# M060A.net
KiCad netlist of a schematic drawn in EAGLE
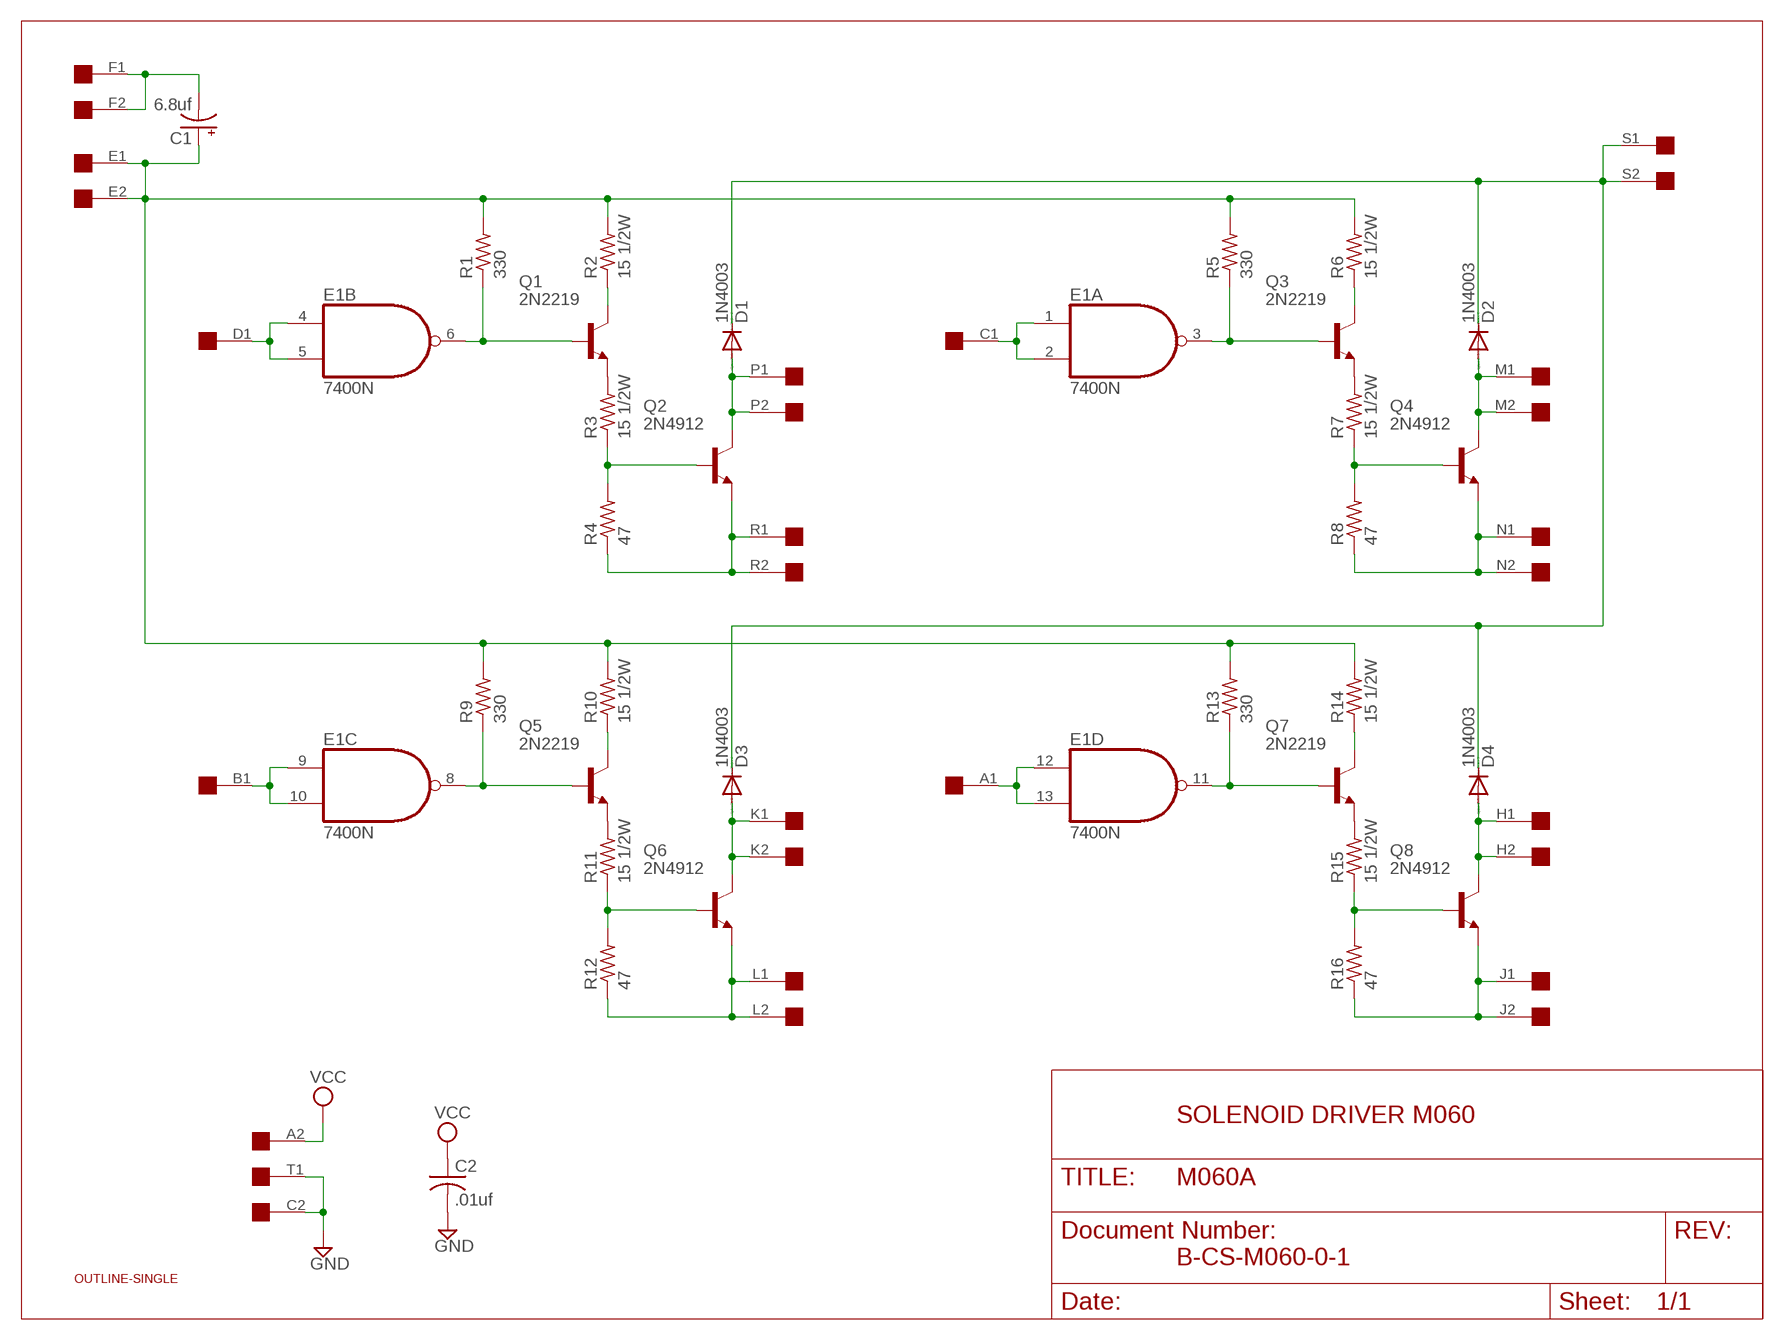
[diagram p0: schematic, sheet 1]

(export (version "E")
  (design (tool "Eeschema 10.0.6"))
  (components
    (comp (ref "C1")
      (value "6.8uf")
      (footprint "eagle-import:E15-5")
      (libsource (lib "eagle-import") (part "CPOL-USE15-5AXIAL"))
    )
    (comp (ref "C2")
      (value ".01uf")
      (footprint "eagle-import:C050-025X075")
      (libsource (lib "eagle-import") (part "C-US050-025X075"))
    )
    (comp (ref "D1")
      (value "1N4003")
      (footprint "eagle-import:DO41-10")
      (libsource (lib "eagle-import") (part "1N4004"))
    )
    (comp (ref "D2")
      (value "1N4003")
      (footprint "eagle-import:DO41-10")
      (libsource (lib "eagle-import") (part "1N4004"))
    )
    (comp (ref "D3")
      (value "1N4003")
      (footprint "eagle-import:DO41-10")
      (libsource (lib "eagle-import") (part "1N4004"))
    )
    (comp (ref "D4")
      (value "1N4003")
      (footprint "eagle-import:DO41-10")
      (libsource (lib "eagle-import") (part "1N4004"))
    )
    (comp (ref "E1")
      (value "7400N")
      (footprint "eagle-import:DIL14")
      (libsource (lib "eagle-import") (part "7400N"))
    )
    (comp (ref "Q1")
      (value "2N2219")
      (footprint "eagle-import:TO5")
      (libsource (lib "eagle-import") (part "2N2219"))
    )
    (comp (ref "Q2")
      (value "2N4912")
      (footprint "eagle-import:TO66")
      (libsource (lib "eagle-import") (part "-NPN-TO66"))
    )
    (comp (ref "Q3")
      (value "2N2219")
      (footprint "eagle-import:TO5")
      (libsource (lib "eagle-import") (part "2N2219"))
    )
    (comp (ref "Q4")
      (value "2N4912")
      (footprint "eagle-import:TO66")
      (libsource (lib "eagle-import") (part "-NPN-TO66"))
    )
    (comp (ref "Q5")
      (value "2N2219")
      (footprint "eagle-import:TO5")
      (libsource (lib "eagle-import") (part "2N2219"))
    )
    (comp (ref "Q6")
      (value "2N4912")
      (footprint "eagle-import:TO66")
      (libsource (lib "eagle-import") (part "-NPN-TO66"))
    )
    (comp (ref "Q7")
      (value "2N2219")
      (footprint "eagle-import:TO5")
      (libsource (lib "eagle-import") (part "2N2219"))
    )
    (comp (ref "Q8")
      (value "2N4912")
      (footprint "eagle-import:TO66")
      (libsource (lib "eagle-import") (part "-NPN-TO66"))
    )
    (comp (ref "R1")
      (value "330")
      (footprint "eagle-import:0207_10")
      (libsource (lib "eagle-import") (part "R-US_0207/10"))
    )
    (comp (ref "R2")
      (value "15 1/2W")
      (footprint "eagle-import:0411_15")
      (libsource (lib "eagle-import") (part "R-US_0411/15"))
    )
    (comp (ref "R3")
      (value "15 1/2W")
      (footprint "eagle-import:0411_15")
      (libsource (lib "eagle-import") (part "R-US_0411/15"))
    )
    (comp (ref "R4")
      (value "47")
      (footprint "eagle-import:0207_10")
      (libsource (lib "eagle-import") (part "R-US_0207/10"))
    )
    (comp (ref "R5")
      (value "330")
      (footprint "eagle-import:0207_10")
      (libsource (lib "eagle-import") (part "R-US_0207/10"))
    )
    (comp (ref "R6")
      (value "15 1/2W")
      (footprint "eagle-import:0411_15")
      (libsource (lib "eagle-import") (part "R-US_0411/15"))
    )
    (comp (ref "R7")
      (value "15 1/2W")
      (footprint "eagle-import:0411_15")
      (libsource (lib "eagle-import") (part "R-US_0411/15"))
    )
    (comp (ref "R8")
      (value "47")
      (footprint "eagle-import:0207_10")
      (libsource (lib "eagle-import") (part "R-US_0207/10"))
    )
    (comp (ref "R9")
      (value "330")
      (footprint "eagle-import:0207_10")
      (libsource (lib "eagle-import") (part "R-US_0207/10"))
    )
    (comp (ref "R10")
      (value "15 1/2W")
      (footprint "eagle-import:0411_15")
      (libsource (lib "eagle-import") (part "R-US_0411/15"))
    )
    (comp (ref "R11")
      (value "15 1/2W")
      (footprint "eagle-import:0411_15")
      (libsource (lib "eagle-import") (part "R-US_0411/15"))
    )
    (comp (ref "R12")
      (value "47")
      (footprint "eagle-import:0207_10")
      (libsource (lib "eagle-import") (part "R-US_0207/10"))
    )
    (comp (ref "R13")
      (value "330")
      (footprint "eagle-import:0207_10")
      (libsource (lib "eagle-import") (part "R-US_0207/10"))
    )
    (comp (ref "R14")
      (value "15 1/2W")
      (footprint "eagle-import:0411_15")
      (libsource (lib "eagle-import") (part "R-US_0411/15"))
    )
    (comp (ref "R15")
      (value "15 1/2W")
      (footprint "eagle-import:0411_15")
      (libsource (lib "eagle-import") (part "R-US_0411/15"))
    )
    (comp (ref "R16")
      (value "47")
      (footprint "eagle-import:0207_10")
      (libsource (lib "eagle-import") (part "R-US_0207/10"))
    )
    (comp (ref "U$1")
      (value "SINGLE")
      (footprint "eagle-import:EDGE-CON2")
      (libsource (lib "eagle-import") (part "SINGLE"))
    )
    (comp (ref "U$2")
      (value "OUTLINE-SINGLE")
      (footprint "eagle-import:SINGLE")
      (libsource (lib "eagle-import") (part "OUTLINE-SINGLE"))
    )
  )
  (nets
    (net (code "1") (name "GND") (class "Default")
      (node (ref "C2") (pin "2") (pinfunction "2_2") (pintype "passive"))
      (node (ref "U$1") (pin "C2") (pinfunction "1_C2") (pintype "bidirectional"))
      (node (ref "U$1") (pin "T1") (pinfunction "1_T1") (pintype "bidirectional"))
    )
    (net (code "2") (name "Net-(E1A-I0)") (class "Default")
      (node (ref "E1") (pin "1") (pinfunction "I0_1") (pintype "input"))
      (node (ref "E1") (pin "2") (pinfunction "I1_2") (pintype "input"))
      (node (ref "U$1") (pin "C1") (pinfunction "1_C1") (pintype "bidirectional"))
    )
    (net (code "3") (name "Net-(E1A-O)") (class "Default")
      (node (ref "E1") (pin "3") (pinfunction "O_3") (pintype "output"))
      (node (ref "Q3") (pin "2") (pinfunction "B_2") (pintype "passive"))
      (node (ref "R5") (pin "1") (pinfunction "1_1") (pintype "passive"))
    )
    (net (code "4") (name "Net-(E1B-I0)") (class "Default")
      (node (ref "E1") (pin "4") (pinfunction "I0_4") (pintype "input"))
      (node (ref "E1") (pin "5") (pinfunction "I1_5") (pintype "input"))
      (node (ref "U$1") (pin "D1") (pinfunction "1_D1") (pintype "bidirectional"))
    )
    (net (code "5") (name "Net-(E1B-O)") (class "Default")
      (node (ref "E1") (pin "6") (pinfunction "O_6") (pintype "output"))
      (node (ref "Q1") (pin "2") (pinfunction "B_2") (pintype "passive"))
      (node (ref "R1") (pin "1") (pinfunction "1_1") (pintype "passive"))
    )
    (net (code "6") (name "Net-(E1C-I0)") (class "Default")
      (node (ref "E1") (pin "10") (pinfunction "I1_10") (pintype "input"))
      (node (ref "E1") (pin "9") (pinfunction "I0_9") (pintype "input"))
      (node (ref "U$1") (pin "B1") (pinfunction "1_B1") (pintype "bidirectional"))
    )
    (net (code "7") (name "Net-(E1C-O)") (class "Default")
      (node (ref "E1") (pin "8") (pinfunction "O_8") (pintype "output"))
      (node (ref "Q5") (pin "2") (pinfunction "B_2") (pintype "passive"))
      (node (ref "R9") (pin "1") (pinfunction "1_1") (pintype "passive"))
    )
    (net (code "8") (name "Net-(E1D-I0)") (class "Default")
      (node (ref "E1") (pin "12") (pinfunction "I0_12") (pintype "input"))
      (node (ref "E1") (pin "13") (pinfunction "I1_13") (pintype "input"))
      (node (ref "U$1") (pin "A1") (pinfunction "1_A1") (pintype "bidirectional"))
    )
    (net (code "9") (name "Net-(E1D-O)") (class "Default")
      (node (ref "E1") (pin "11") (pinfunction "O_11") (pintype "output"))
      (node (ref "Q7") (pin "2") (pinfunction "B_2") (pintype "passive"))
      (node (ref "R13") (pin "1") (pinfunction "1_1") (pintype "passive"))
    )
    (net (code "10") (name "Net-(Q1-C)") (class "Default")
      (node (ref "Q1") (pin "3") (pinfunction "C_3") (pintype "passive"))
      (node (ref "R2") (pin "1") (pinfunction "1_1") (pintype "passive"))
    )
    (net (code "11") (name "Net-(Q1-E)") (class "Default")
      (node (ref "Q1") (pin "1") (pinfunction "E_1") (pintype "passive"))
      (node (ref "R3") (pin "2") (pinfunction "2_2") (pintype "passive"))
    )
    (net (code "12") (name "Net-(Q2-B)") (class "Default")
      (node (ref "Q2") (pin "2") (pinfunction "B_2") (pintype "passive"))
      (node (ref "R3") (pin "1") (pinfunction "1_1") (pintype "passive"))
      (node (ref "R4") (pin "2") (pinfunction "2_2") (pintype "passive"))
    )
    (net (code "13") (name "Net-(Q2-C)") (class "Default")
      (node (ref "D1") (pin "A") (pinfunction "A_A") (pintype "passive"))
      (node (ref "Q2") (pin "3") (pinfunction "C_3") (pintype "passive"))
      (node (ref "U$1") (pin "P1") (pinfunction "1_P1") (pintype "bidirectional"))
      (node (ref "U$1") (pin "P2") (pinfunction "1_P2") (pintype "bidirectional"))
    )
    (net (code "14") (name "Net-(Q2-E)") (class "Default")
      (node (ref "Q2") (pin "1") (pinfunction "E_1") (pintype "passive"))
      (node (ref "R4") (pin "1") (pinfunction "1_1") (pintype "passive"))
      (node (ref "U$1") (pin "R1") (pinfunction "1_R1") (pintype "bidirectional"))
      (node (ref "U$1") (pin "R2") (pinfunction "1_R2") (pintype "bidirectional"))
    )
    (net (code "15") (name "Net-(Q3-C)") (class "Default")
      (node (ref "Q3") (pin "3") (pinfunction "C_3") (pintype "passive"))
      (node (ref "R6") (pin "1") (pinfunction "1_1") (pintype "passive"))
    )
    (net (code "16") (name "Net-(Q3-E)") (class "Default")
      (node (ref "Q3") (pin "1") (pinfunction "E_1") (pintype "passive"))
      (node (ref "R7") (pin "2") (pinfunction "2_2") (pintype "passive"))
    )
    (net (code "17") (name "Net-(Q4-B)") (class "Default")
      (node (ref "Q4") (pin "2") (pinfunction "B_2") (pintype "passive"))
      (node (ref "R7") (pin "1") (pinfunction "1_1") (pintype "passive"))
      (node (ref "R8") (pin "2") (pinfunction "2_2") (pintype "passive"))
    )
    (net (code "18") (name "Net-(Q4-C)") (class "Default")
      (node (ref "D2") (pin "A") (pinfunction "A_A") (pintype "passive"))
      (node (ref "Q4") (pin "3") (pinfunction "C_3") (pintype "passive"))
      (node (ref "U$1") (pin "M1") (pinfunction "1_M1") (pintype "bidirectional"))
      (node (ref "U$1") (pin "M2") (pinfunction "1_M2") (pintype "bidirectional"))
    )
    (net (code "19") (name "Net-(Q4-E)") (class "Default")
      (node (ref "Q4") (pin "1") (pinfunction "E_1") (pintype "passive"))
      (node (ref "R8") (pin "1") (pinfunction "1_1") (pintype "passive"))
      (node (ref "U$1") (pin "N1") (pinfunction "1_N1") (pintype "bidirectional"))
      (node (ref "U$1") (pin "N2") (pinfunction "1_N2") (pintype "bidirectional"))
    )
    (net (code "20") (name "Net-(Q5-C)") (class "Default")
      (node (ref "Q5") (pin "3") (pinfunction "C_3") (pintype "passive"))
      (node (ref "R10") (pin "1") (pinfunction "1_1") (pintype "passive"))
    )
    (net (code "21") (name "Net-(Q5-E)") (class "Default")
      (node (ref "Q5") (pin "1") (pinfunction "E_1") (pintype "passive"))
      (node (ref "R11") (pin "2") (pinfunction "2_2") (pintype "passive"))
    )
    (net (code "22") (name "Net-(Q6-B)") (class "Default")
      (node (ref "Q6") (pin "2") (pinfunction "B_2") (pintype "passive"))
      (node (ref "R11") (pin "1") (pinfunction "1_1") (pintype "passive"))
      (node (ref "R12") (pin "2") (pinfunction "2_2") (pintype "passive"))
    )
    (net (code "23") (name "Net-(Q6-C)") (class "Default")
      (node (ref "D3") (pin "A") (pinfunction "A_A") (pintype "passive"))
      (node (ref "Q6") (pin "3") (pinfunction "C_3") (pintype "passive"))
      (node (ref "U$1") (pin "K1") (pinfunction "1_K1") (pintype "bidirectional"))
      (node (ref "U$1") (pin "K2") (pinfunction "1_K2") (pintype "bidirectional"))
    )
    (net (code "24") (name "Net-(Q6-E)") (class "Default")
      (node (ref "Q6") (pin "1") (pinfunction "E_1") (pintype "passive"))
      (node (ref "R12") (pin "1") (pinfunction "1_1") (pintype "passive"))
      (node (ref "U$1") (pin "L1") (pinfunction "1_L1") (pintype "bidirectional"))
      (node (ref "U$1") (pin "L2") (pinfunction "1_L2") (pintype "bidirectional"))
    )
    (net (code "25") (name "Net-(Q7-C)") (class "Default")
      (node (ref "Q7") (pin "3") (pinfunction "C_3") (pintype "passive"))
      (node (ref "R14") (pin "1") (pinfunction "1_1") (pintype "passive"))
    )
    (net (code "26") (name "Net-(Q7-E)") (class "Default")
      (node (ref "Q7") (pin "1") (pinfunction "E_1") (pintype "passive"))
      (node (ref "R15") (pin "2") (pinfunction "2_2") (pintype "passive"))
    )
    (net (code "27") (name "Net-(Q8-B)") (class "Default")
      (node (ref "Q8") (pin "2") (pinfunction "B_2") (pintype "passive"))
      (node (ref "R15") (pin "1") (pinfunction "1_1") (pintype "passive"))
      (node (ref "R16") (pin "2") (pinfunction "2_2") (pintype "passive"))
    )
    (net (code "28") (name "Net-(Q8-C)") (class "Default")
      (node (ref "D4") (pin "A") (pinfunction "A_A") (pintype "passive"))
      (node (ref "Q8") (pin "3") (pinfunction "C_3") (pintype "passive"))
      (node (ref "U$1") (pin "H1") (pinfunction "1_H1") (pintype "bidirectional"))
      (node (ref "U$1") (pin "H2") (pinfunction "1_H2") (pintype "bidirectional"))
    )
    (net (code "29") (name "Net-(Q8-E)") (class "Default")
      (node (ref "Q8") (pin "1") (pinfunction "E_1") (pintype "passive"))
      (node (ref "R16") (pin "1") (pinfunction "1_1") (pintype "passive"))
      (node (ref "U$1") (pin "J1") (pinfunction "1_J1") (pintype "bidirectional"))
      (node (ref "U$1") (pin "J2") (pinfunction "1_J2") (pintype "bidirectional"))
    )
    (net (code "30") (name "Net-(U$1AC-1)") (class "Default")
      (node (ref "D1") (pin "C") (pinfunction "C_C") (pintype "passive"))
      (node (ref "D2") (pin "C") (pinfunction "C_C") (pintype "passive"))
      (node (ref "D3") (pin "C") (pinfunction "C_C") (pintype "passive"))
      (node (ref "D4") (pin "C") (pinfunction "C_C") (pintype "passive"))
      (node (ref "U$1") (pin "S1") (pinfunction "1_S1") (pintype "bidirectional"))
      (node (ref "U$1") (pin "S2") (pinfunction "1_S2") (pintype "bidirectional"))
    )
    (net (code "31") (name "Net-(U$1I-1)") (class "Default")
      (node (ref "C1") (pin "+") (pinfunction "+_+") (pintype "passive"))
      (node (ref "R1") (pin "2") (pinfunction "2_2") (pintype "passive"))
      (node (ref "R10") (pin "2") (pinfunction "2_2") (pintype "passive"))
      (node (ref "R13") (pin "2") (pinfunction "2_2") (pintype "passive"))
      (node (ref "R14") (pin "2") (pinfunction "2_2") (pintype "passive"))
      (node (ref "R2") (pin "2") (pinfunction "2_2") (pintype "passive"))
      (node (ref "R5") (pin "2") (pinfunction "2_2") (pintype "passive"))
      (node (ref "R6") (pin "2") (pinfunction "2_2") (pintype "passive"))
      (node (ref "R9") (pin "2") (pinfunction "2_2") (pintype "passive"))
      (node (ref "U$1") (pin "E1") (pinfunction "1_E1") (pintype "bidirectional"))
      (node (ref "U$1") (pin "E2") (pinfunction "1_E2") (pintype "bidirectional"))
    )
    (net (code "32") (name "Net-(U$1K-1)") (class "Default")
      (node (ref "C1") (pin "-") (pinfunction "-_-") (pintype "passive"))
      (node (ref "U$1") (pin "F1") (pinfunction "1_F1") (pintype "bidirectional"))
      (node (ref "U$1") (pin "F2") (pinfunction "1_F2") (pintype "bidirectional"))
    )
    (net (code "33") (name "VCC") (class "Default")
      (node (ref "C2") (pin "1") (pinfunction "1_1") (pintype "passive"))
      (node (ref "U$1") (pin "A2") (pinfunction "1_A2") (pintype "bidirectional"))
    )
  )
)
